# Nguyen_Ly.net
KiCad netlist of a schematic drawn in Altium Designer
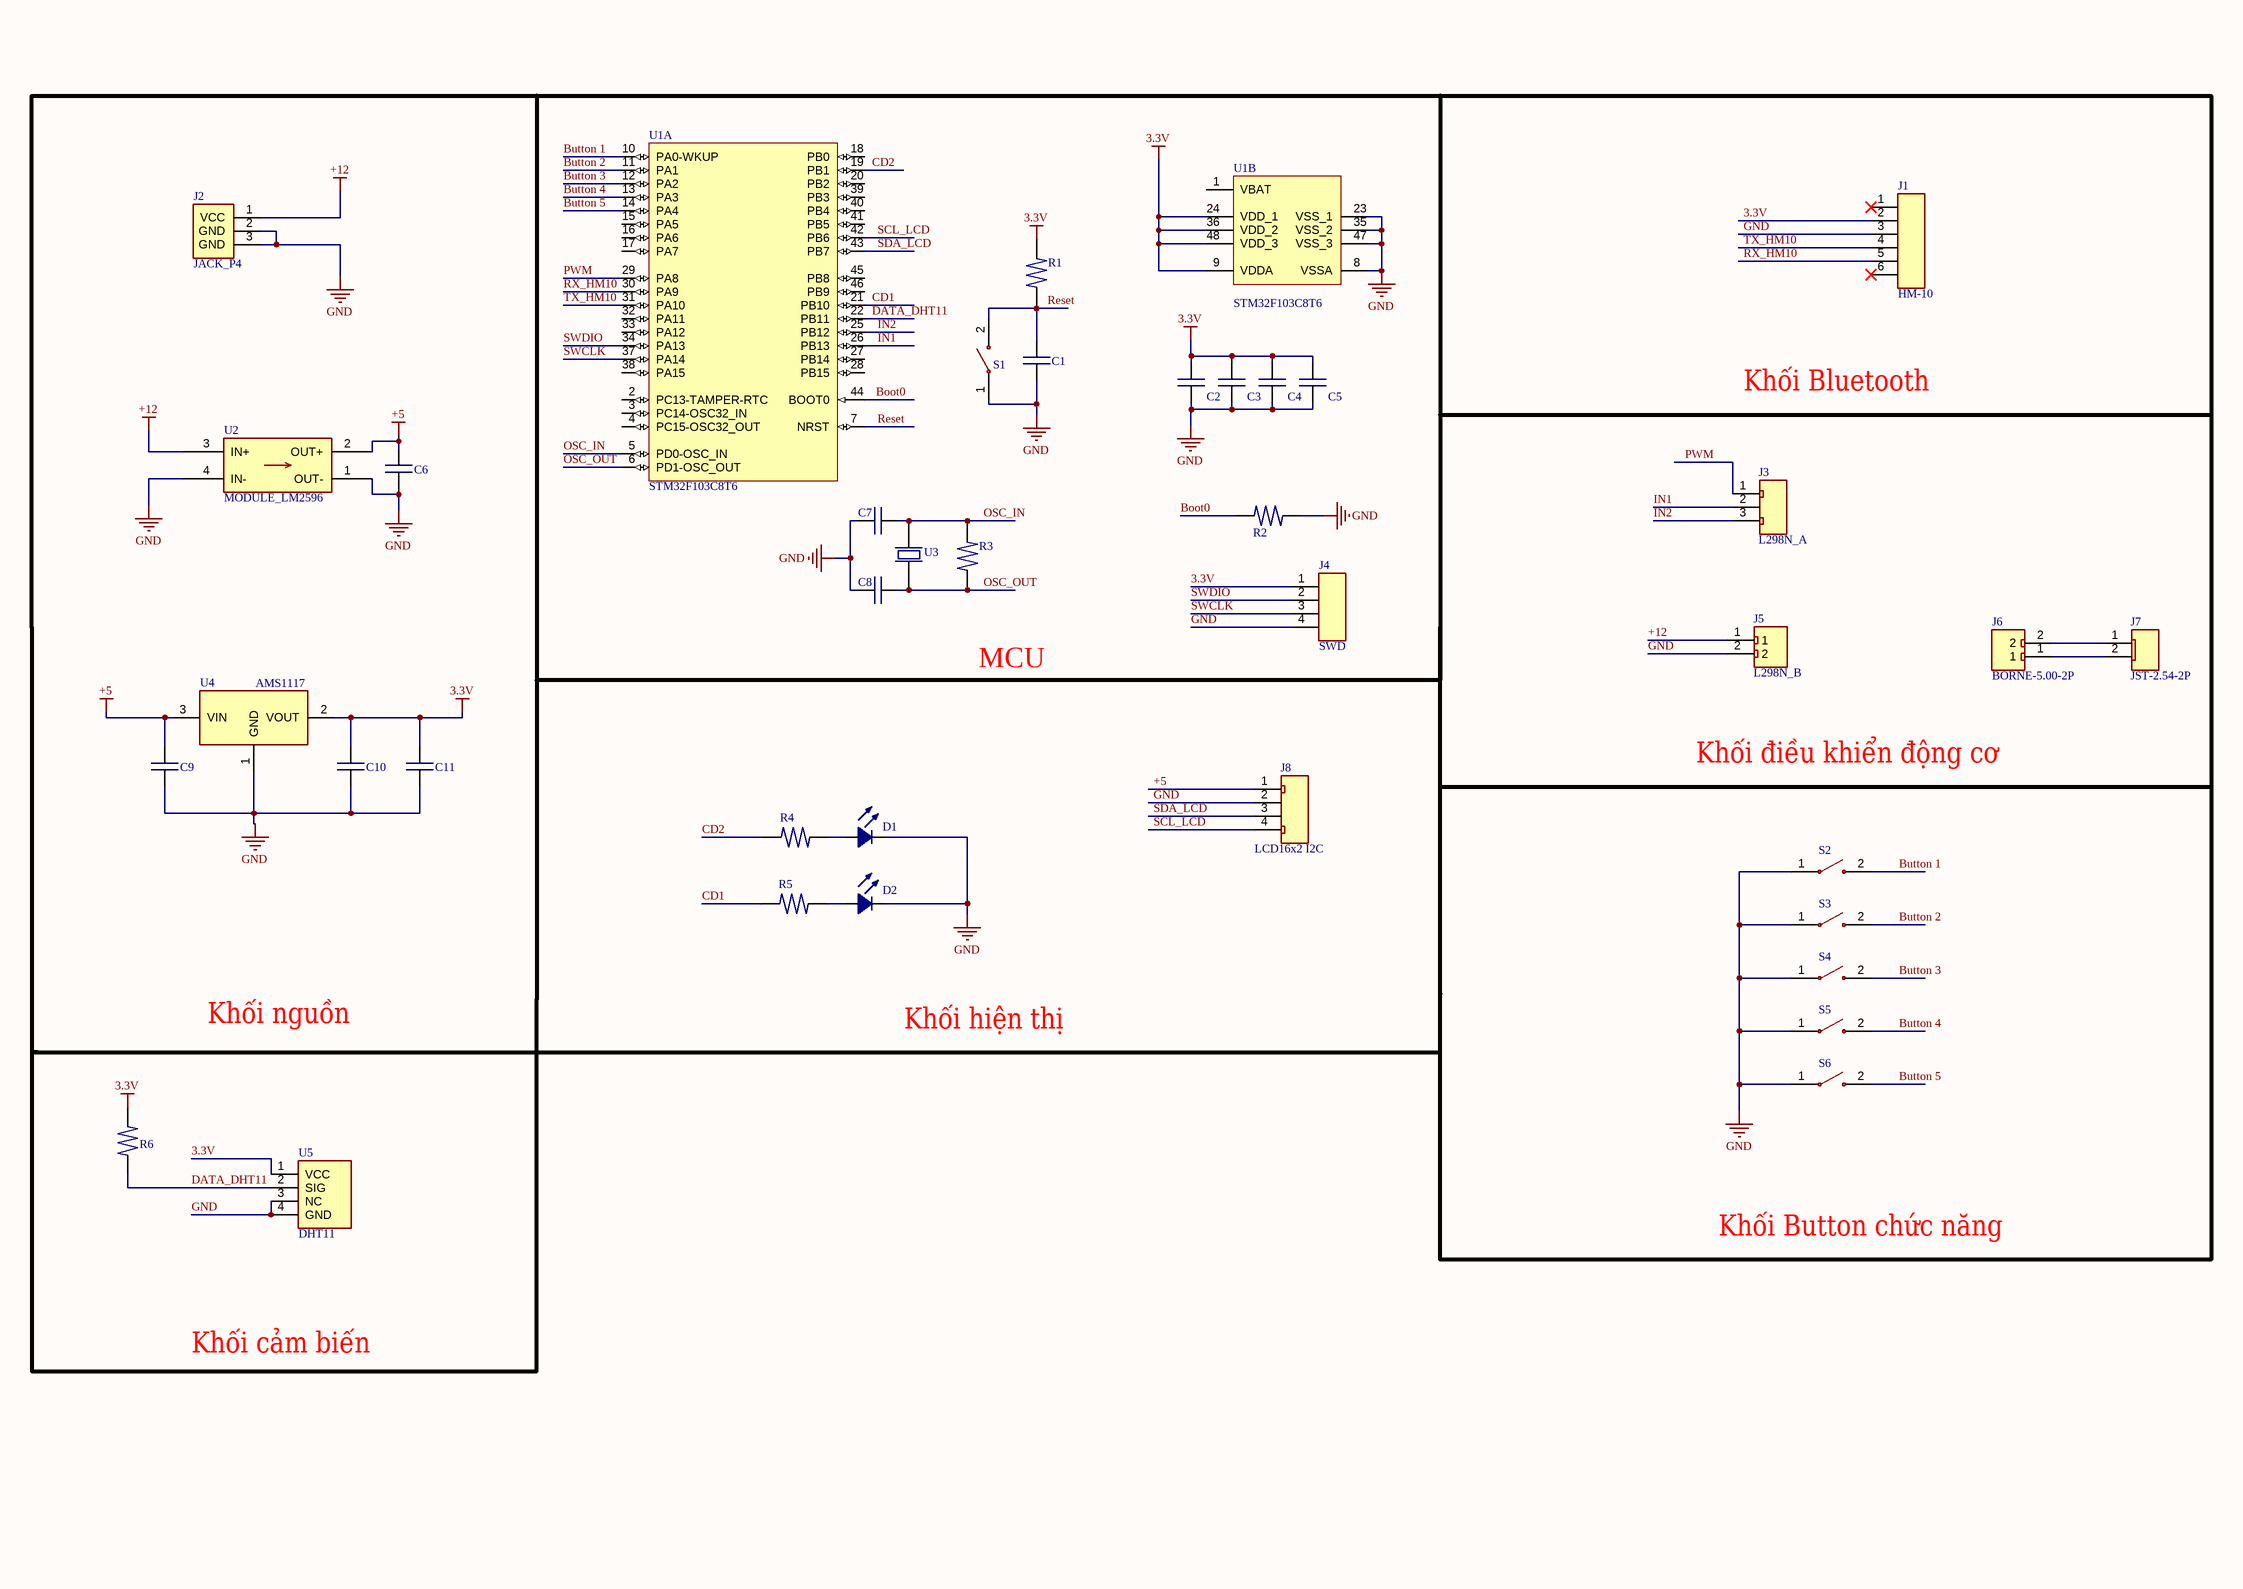
[diagram p0: Nguyen_Ly.SchDoc]

(export (version "E")
  (design (tool "Eeschema 10.0.6"))
  (components
    (comp (ref "C1")
      (value "CAPCITOR 104")
      (footprint "CAPACITOR 104")
      (description "Ceramic Capacitor 104, 3mm.")
      (libsource (lib "MyComponents") (part "CAPACITOR 104"))
    )
    (comp (ref "C2")
      (value "CAPACITOR 0603")
      (footprint "CAPACITOR 0603")
      (description "Generic Capacitor 0603, 1.6x0.8x0.9mm.")
      (libsource (lib "MyComponents") (part "CAPACITOR 0603"))
    )
    (comp (ref "C3")
      (value "CAPACITOR 0603")
      (footprint "CAPACITOR 0603")
      (description "Generic Capacitor 0603, 1.6x0.8x0.9mm.")
      (libsource (lib "MyComponents") (part "CAPACITOR 0603"))
    )
    (comp (ref "C4")
      (value "CAPACITOR 0603")
      (footprint "CAPACITOR 0603")
      (description "Generic Capacitor 0603, 1.6x0.8x0.9mm.")
      (libsource (lib "MyComponents") (part "CAPACITOR 0603"))
    )
    (comp (ref "C5")
      (value "CAPACITOR 0603")
      (footprint "CAPACITOR 0603")
      (description "Generic Capacitor 0603, 1.6x0.8x0.9mm.")
      (libsource (lib "MyComponents") (part "CAPACITOR 0603"))
    )
    (comp (ref "C6")
      (value "CAPCITOR 104")
      (footprint "CAPACITOR 104")
      (description "Ceramic Capacitor 104, 3mm.")
      (libsource (lib "MyComponents") (part "CAPACITOR 104"))
    )
    (comp (ref "C7")
      (value "CAPACITOR 0603")
      (footprint "CAPACITOR 0603")
      (description "Generic Capacitor 0603, 1.6x0.8x0.9mm.")
      (libsource (lib "MyComponents") (part "CAPACITOR 0603"))
    )
    (comp (ref "C8")
      (value "CAPACITOR 0603")
      (footprint "CAPACITOR 0603")
      (description "Generic Capacitor 0603, 1.6x0.8x0.9mm.")
      (libsource (lib "MyComponents") (part "CAPACITOR 0603"))
    )
    (comp (ref "C9")
      (value "CAPACITOR 0603")
      (footprint "CAPACITOR 0603")
      (description "Generic Capacitor 0603, 1.6x0.8x0.9mm.")
      (libsource (lib "MyComponents") (part "CAPACITOR 0603"))
    )
    (comp (ref "C10")
      (value "CAPACITOR 0603")
      (footprint "CAPACITOR 0603")
      (description "Generic Capacitor 0603, 1.6x0.8x0.9mm.")
      (libsource (lib "MyComponents") (part "CAPACITOR 0603"))
    )
    (comp (ref "C11")
      (value "CAPACITOR 0603")
      (footprint "CAPACITOR 0603")
      (description "Generic Capacitor 0603, 1.6x0.8x0.9mm.")
      (libsource (lib "MyComponents") (part "CAPACITOR 0603"))
    )
    (comp (ref "D1")
      (value "LED_5mm_YELLOW")
      (footprint "LED_5mm_YELLOW")
      (description "LED PTH 5mm Yellow.")
      (libsource (lib "MyComponents") (part "LED_5mm_YELLOW"))
    )
    (comp (ref "D2")
      (value "LED_5mm_RED")
      (footprint "LED_5mm_RED")
      (description "LED PTH 5mm Red.")
      (libsource (lib "MyComponents") (part "LED_5mm_RED"))
    )
    (comp (ref "J1")
      (value "HM-10")
      (footprint "FEMALE-2.54-6P")
      (description "Female Header Connector 2.54mm 6 Pins.")
      (libsource (lib "MyComponents") (part "FEMALE-2.54-6P"))
    )
    (comp (ref "J2")
      (value "JACK_P4")
      (footprint "JACK_P4")
      (description "9V Battery Connector Jack P4.")
      (libsource (lib "MyComponents") (part "JACK_P4"))
    )
    (comp (ref "J3")
      (value "L298N_A")
      (footprint "JST-2.54-3P")
      (description "Female Connector JST 3 Vias, 2.54mm.")
      (libsource (lib "MyComponents") (part "JST-2.54-3P"))
    )
    (comp (ref "J4")
      (value "SWD")
      (footprint "MALE-2.54-4P")
      (description "Male Header Connector 2.54mm 4 Pins.")
      (libsource (lib "MyComponents") (part "MALE-2.54-4P"))
    )
    (comp (ref "J5")
      (value "L298N_B")
      (footprint "BORNE-5.00-2P")
      (description "Borne 2 Vias, Pitch 5mm.")
      (libsource (lib "") (part "BORNE-5.00-2P_1"))
    )
    (comp (ref "J6")
      (value "BORNE-5.00-2P")
      (footprint "BORNE-5.00-2P")
      (description "Borne 2 Vias, Pitch 5mm.")
      (libsource (lib "MyComponents") (part "BORNE-5.00-2P"))
    )
    (comp (ref "J7")
      (value "JST-2.54-2P")
      (footprint "JST-2.54-2P")
      (description "Female Connector JST 2 Vias, 2.54mm.")
      (libsource (lib "MyComponents") (part "JST-2.54-2P"))
    )
    (comp (ref "J8")
      (value "LCD16x2 I2C")
      (footprint "JST-2.54-4P")
      (description "Female Connector JST 4 Vias, 2.54mm.")
      (libsource (lib "MyComponents") (part "JST-2.54-4P"))
    )
    (comp (ref "R1")
      (value "RESISTOR_9.5mm")
      (footprint "RESISTOR_PTH_9.5mm")
      (description "Generic Resistor 9.5mm.")
      (libsource (lib "MyComponents") (part "RESISTOR_9.5mm"))
    )
    (comp (ref "R2")
      (value "RESISTOR_0603")
      (footprint "RESISTOR_0603")
      (description "Generic Resistor 0603.")
      (libsource (lib "MyComponents") (part "RESISTOR_0603"))
    )
    (comp (ref "R3")
      (value "RESISTOR_0603")
      (footprint "RESISTOR_0603")
      (description "Generic Resistor 0603.")
      (libsource (lib "MyComponents") (part "RESISTOR_0603"))
    )
    (comp (ref "R4")
      (value "RESISTOR_9.5mm")
      (footprint "RESISTOR_PTH_9.5mm")
      (description "Generic Resistor 9.5mm.")
      (libsource (lib "MyComponents") (part "RESISTOR_9.5mm"))
    )
    (comp (ref "R5")
      (value "RESISTOR_9.5mm")
      (footprint "RESISTOR_PTH_9.5mm")
      (description "Generic Resistor 9.5mm.")
      (libsource (lib "MyComponents") (part "RESISTOR_9.5mm"))
    )
    (comp (ref "R6")
      (value "RESISTOR_9.5mm")
      (footprint "RESISTOR_PTH_9.5mm")
      (description "Generic Resistor 9.5mm.")
      (libsource (lib "MyComponents") (part "RESISTOR_9.5mm"))
    )
    (comp (ref "S1")
      (value "PUSH_BUTTON_6X6")
      (footprint "PUSH_BUTTON_6X6")
      (description "Push Button Tactile Switch PTH 4 Pins 6x6mm.")
      (libsource (lib "") (part "PUSH_BUTTON_6X6_1"))
    )
    (comp (ref "S2")
      (value "PUSH_BUTTON_6X6")
      (footprint "PUSH_BUTTON_6X6")
      (description "Push Button Tactile Switch PTH 4 Pins 6x6mm.")
      (libsource (lib "MyComponents") (part "PUSH_BUTTON_6X6"))
    )
    (comp (ref "S3")
      (value "PUSH_BUTTON_6X6")
      (footprint "PUSH_BUTTON_6X6")
      (description "Push Button Tactile Switch PTH 4 Pins 6x6mm.")
      (libsource (lib "MyComponents") (part "PUSH_BUTTON_6X6"))
    )
    (comp (ref "S4")
      (value "PUSH_BUTTON_6X6")
      (footprint "PUSH_BUTTON_6X6")
      (description "Push Button Tactile Switch PTH 4 Pins 6x6mm.")
      (libsource (lib "MyComponents") (part "PUSH_BUTTON_6X6"))
    )
    (comp (ref "S5")
      (value "PUSH_BUTTON_6X6")
      (footprint "PUSH_BUTTON_6X6")
      (description "Push Button Tactile Switch PTH 4 Pins 6x6mm.")
      (libsource (lib "MyComponents") (part "PUSH_BUTTON_6X6"))
    )
    (comp (ref "S6")
      (value "PUSH_BUTTON_6X6")
      (footprint "PUSH_BUTTON_6X6")
      (description "Push Button Tactile Switch PTH 4 Pins 6x6mm.")
      (libsource (lib "MyComponents") (part "PUSH_BUTTON_6X6"))
    )
    (comp (ref "U1")
      (value "STM32F103C8T6")
      (footprint "STM-LQFP48_N")
      (libsource (lib "STMicroelectronics STM32 F1") (part "STM32F103C8T6"))
    )
    (comp (ref "U2")
      (value "MODULE_LM2596")
      (footprint "MODULE_LM2596")
      (description "MODULE BUCK STEP DOWN 3A 43x20mm")
      (libsource (lib "MyComponents") (part "MODULE_LM2596"))
    )
    (comp (ref "U3")
      (value "CRISTAL_16Mhz")
      (footprint "CRISTAL_16Mhz_SMD")
      (description "CRYSTAL 16MHZ, PTH and SMD")
      (libsource (lib "MyComponents") (part "CRISTAL_16Mhz"))
    )
    (comp (ref "U4")
      (value "AMS1117")
      (footprint "AMS1117")
      (description "IC REG LINEAR 1A SOT-89-3L")
      (libsource (lib "MyComponents") (part "AMS1117"))
    )
    (comp (ref "U5")
      (value "DHT11")
      (footprint "DHT11")
      (description "SENSOR HUMIDITY/TEMPERATURE")
      (libsource (lib "MyComponents") (part "DHT11"))
    )
  )
  (nets
    (net (code "1") (name "+5") (class "Default")
      (node (ref "C6") (pin "2") (pinfunction "2_2") (pintype "passive"))
      (node (ref "C9") (pin "2") (pinfunction "2_2") (pintype "passive"))
      (node (ref "J8") (pin "1") (pintype "passive"))
      (node (ref "U2") (pin "2") (pinfunction "OUT+_2") (pintype "passive"))
      (node (ref "U4") (pin "3") (pinfunction "VIN_3") (pintype "passive"))
    )
    (net (code "2") (name "+12") (class "Default")
      (node (ref "J2") (pin "1") (pinfunction "VCC_1") (pintype "passive"))
      (node (ref "J5") (pin "1") (pinfunction "1_1") (pintype "passive"))
      (node (ref "U2") (pin "3") (pinfunction "IN+_3") (pintype "passive"))
    )
    (net (code "3") (name "/Boot0") (class "Default")
      (node (ref "R2") (pin "2") (pinfunction "2_2") (pintype "passive"))
      (node (ref "U1") (pin "44") (pinfunction "BOOT0_44") (pintype "input"))
    )
    (net (code "4") (name "/Button 1") (class "Default")
      (node (ref "S2") (pin "2") (pinfunction "2_2") (pintype "passive"))
      (node (ref "U1") (pin "10") (pinfunction "PA0-WKUP_10") (pintype "bidirectional"))
    )
    (net (code "5") (name "/Button 2") (class "Default")
      (node (ref "S3") (pin "2") (pinfunction "2_2") (pintype "passive"))
      (node (ref "U1") (pin "11") (pinfunction "PA1_11") (pintype "bidirectional"))
    )
    (net (code "6") (name "/Button 3") (class "Default")
      (node (ref "S4") (pin "2") (pinfunction "2_2") (pintype "passive"))
      (node (ref "U1") (pin "12") (pinfunction "PA2_12") (pintype "bidirectional"))
    )
    (net (code "7") (name "/Button 4") (class "Default")
      (node (ref "S5") (pin "2") (pinfunction "2_2") (pintype "passive"))
      (node (ref "U1") (pin "13") (pinfunction "PA3_13") (pintype "bidirectional"))
    )
    (net (code "8") (name "/Button 5") (class "Default")
      (node (ref "S6") (pin "2") (pinfunction "2_2") (pintype "passive"))
      (node (ref "U1") (pin "14") (pinfunction "PA4_14") (pintype "bidirectional"))
    )
    (net (code "9") (name "/CD1") (class "Default")
      (node (ref "R5") (pin "1") (pinfunction "1_1") (pintype "passive"))
      (node (ref "U1") (pin "21") (pinfunction "PB10_21") (pintype "bidirectional"))
    )
    (net (code "10") (name "/CD2") (class "Default")
      (node (ref "R4") (pin "1") (pinfunction "1_1") (pintype "passive"))
      (node (ref "U1") (pin "19") (pinfunction "PB1_19") (pintype "bidirectional"))
    )
    (net (code "11") (name "/DATA_DHT11") (class "Default")
      (node (ref "R6") (pin "1") (pinfunction "1_1") (pintype "passive"))
      (node (ref "U1") (pin "22") (pinfunction "PB11_22") (pintype "bidirectional"))
      (node (ref "U5") (pin "2") (pinfunction "SIG_2") (pintype "passive"))
    )
    (net (code "12") (name "/IN1") (class "Default")
      (node (ref "J3") (pin "2") (pintype "passive"))
      (node (ref "U1") (pin "26") (pinfunction "PB13_26") (pintype "bidirectional"))
    )
    (net (code "13") (name "/IN2") (class "Default")
      (node (ref "J3") (pin "3") (pintype "passive"))
      (node (ref "U1") (pin "25") (pinfunction "PB12_25") (pintype "bidirectional"))
    )
    (net (code "14") (name "/OSC_IN") (class "Default")
      (node (ref "C7") (pin "2") (pinfunction "2_2") (pintype "passive"))
      (node (ref "R3") (pin "2") (pinfunction "2_2") (pintype "passive"))
      (node (ref "U1") (pin "5") (pinfunction "PD0-OSC_IN_5") (pintype "bidirectional"))
      (node (ref "U3") (pin "2") (pinfunction "2_2") (pintype "power_in"))
    )
    (net (code "15") (name "/OSC_OUT") (class "Default")
      (node (ref "C8") (pin "2") (pinfunction "2_2") (pintype "passive"))
      (node (ref "R3") (pin "1") (pinfunction "1_1") (pintype "passive"))
      (node (ref "U1") (pin "6") (pinfunction "PD1-OSC_OUT_6") (pintype "bidirectional"))
      (node (ref "U3") (pin "1") (pinfunction "1_1") (pintype "power_in"))
    )
    (net (code "16") (name "/PWM") (class "Default")
      (node (ref "J3") (pin "1") (pintype "passive"))
      (node (ref "U1") (pin "29") (pinfunction "PA8_29") (pintype "bidirectional"))
    )
    (net (code "17") (name "/RX_HM10") (class "Default")
      (node (ref "J1") (pin "5") (pintype "passive"))
      (node (ref "U1") (pin "30") (pinfunction "PA9_30") (pintype "bidirectional"))
    )
    (net (code "18") (name "/Reset") (class "Default")
      (node (ref "C1") (pin "2") (pinfunction "2_2") (pintype "passive"))
      (node (ref "R1") (pin "1") (pinfunction "1_1") (pintype "passive"))
      (node (ref "S1") (pin "2") (pinfunction "2_2") (pintype "passive"))
      (node (ref "U1") (pin "7") (pinfunction "NRST_7") (pintype "bidirectional"))
    )
    (net (code "19") (name "/SCL_LCD") (class "Default")
      (node (ref "J8") (pin "4") (pintype "passive"))
      (node (ref "U1") (pin "42") (pinfunction "PB6_42") (pintype "bidirectional"))
    )
    (net (code "20") (name "/SDA_LCD") (class "Default")
      (node (ref "J8") (pin "3") (pintype "passive"))
      (node (ref "U1") (pin "43") (pinfunction "PB7_43") (pintype "bidirectional"))
    )
    (net (code "21") (name "/SWCLK") (class "Default")
      (node (ref "J4") (pin "3") (pintype "passive"))
      (node (ref "U1") (pin "37") (pinfunction "PA14_37") (pintype "bidirectional"))
    )
    (net (code "22") (name "/SWDIO") (class "Default")
      (node (ref "J4") (pin "2") (pintype "passive"))
      (node (ref "U1") (pin "34") (pinfunction "PA13_34") (pintype "bidirectional"))
    )
    (net (code "23") (name "/TX_HM10") (class "Default")
      (node (ref "J1") (pin "4") (pintype "passive"))
      (node (ref "U1") (pin "31") (pinfunction "PA10_31") (pintype "bidirectional"))
    )
    (net (code "24") (name "3.3V") (class "Default")
      (node (ref "C10") (pin "2") (pinfunction "2_2") (pintype "passive"))
      (node (ref "C11") (pin "2") (pinfunction "2_2") (pintype "passive"))
      (node (ref "C2") (pin "2") (pinfunction "2_2") (pintype "passive"))
      (node (ref "C3") (pin "2") (pinfunction "2_2") (pintype "passive"))
      (node (ref "C4") (pin "2") (pinfunction "2_2") (pintype "passive"))
      (node (ref "C5") (pin "2") (pinfunction "2_2") (pintype "passive"))
      (node (ref "J1") (pin "2") (pintype "passive"))
      (node (ref "J4") (pin "1") (pintype "passive"))
      (node (ref "R1") (pin "2") (pinfunction "2_2") (pintype "passive"))
      (node (ref "R6") (pin "2") (pinfunction "2_2") (pintype "passive"))
      (node (ref "U1") (pin "24") (pinfunction "VDD_1_24") (pintype "power_in"))
      (node (ref "U1") (pin "36") (pinfunction "VDD_2_36") (pintype "power_in"))
      (node (ref "U1") (pin "48") (pinfunction "VDD_3_48") (pintype "power_in"))
      (node (ref "U1") (pin "9") (pinfunction "VDDA_9") (pintype "power_in"))
      (node (ref "U4") (pin "2") (pinfunction "VOUT_2") (pintype "passive"))
      (node (ref "U5") (pin "1") (pinfunction "VCC_1") (pintype "passive"))
    )
    (net (code "25") (name "GND") (class "Default")
      (node (ref "C1") (pin "1") (pinfunction "1_1") (pintype "passive"))
      (node (ref "C10") (pin "1") (pinfunction "1_1") (pintype "passive"))
      (node (ref "C11") (pin "1") (pinfunction "1_1") (pintype "passive"))
      (node (ref "C2") (pin "1") (pinfunction "1_1") (pintype "passive"))
      (node (ref "C3") (pin "1") (pinfunction "1_1") (pintype "passive"))
      (node (ref "C4") (pin "1") (pinfunction "1_1") (pintype "passive"))
      (node (ref "C5") (pin "1") (pinfunction "1_1") (pintype "passive"))
      (node (ref "C6") (pin "1") (pinfunction "1_1") (pintype "passive"))
      (node (ref "C7") (pin "1") (pinfunction "1_1") (pintype "passive"))
      (node (ref "C8") (pin "1") (pinfunction "1_1") (pintype "passive"))
      (node (ref "C9") (pin "1") (pinfunction "1_1") (pintype "passive"))
      (node (ref "D1") (pin "2") (pinfunction "2_2") (pintype "passive"))
      (node (ref "D2") (pin "2") (pinfunction "2_2") (pintype "passive"))
      (node (ref "J1") (pin "3") (pintype "passive"))
      (node (ref "J2") (pin "2") (pinfunction "GND_2") (pintype "passive"))
      (node (ref "J2") (pin "3") (pinfunction "GND_3") (pintype "passive"))
      (node (ref "J4") (pin "4") (pintype "passive"))
      (node (ref "J5") (pin "2") (pinfunction "2_2") (pintype "passive"))
      (node (ref "J8") (pin "2") (pintype "passive"))
      (node (ref "R2") (pin "1") (pinfunction "1_1") (pintype "passive"))
      (node (ref "S1") (pin "1") (pinfunction "1_1") (pintype "passive"))
      (node (ref "S2") (pin "1") (pinfunction "1_1") (pintype "passive"))
      (node (ref "S3") (pin "1") (pinfunction "1_1") (pintype "passive"))
      (node (ref "S4") (pin "1") (pinfunction "1_1") (pintype "passive"))
      (node (ref "S5") (pin "1") (pinfunction "1_1") (pintype "passive"))
      (node (ref "S6") (pin "1") (pinfunction "1_1") (pintype "passive"))
      (node (ref "U1") (pin "23") (pinfunction "VSS_1_23") (pintype "power_in"))
      (node (ref "U1") (pin "35") (pinfunction "VSS_2_35") (pintype "power_in"))
      (node (ref "U1") (pin "47") (pinfunction "VSS_3_47") (pintype "power_in"))
      (node (ref "U1") (pin "8") (pinfunction "VSSA_8") (pintype "power_in"))
      (node (ref "U2") (pin "1") (pinfunction "OUT-_1") (pintype "passive"))
      (node (ref "U2") (pin "4") (pinfunction "IN-_4") (pintype "passive"))
      (node (ref "U4") (pin "1") (pinfunction "GND_1") (pintype "passive"))
      (node (ref "U5") (pin "3") (pinfunction "NC_3") (pintype "passive"))
      (node (ref "U5") (pin "4") (pinfunction "GND_4") (pintype "passive"))
    )
    (net (code "26") (name "Net-(D1-Pad1)") (class "Default")
      (node (ref "D1") (pin "1") (pinfunction "1_1") (pintype "passive"))
      (node (ref "R4") (pin "2") (pinfunction "2_2") (pintype "passive"))
    )
    (net (code "27") (name "Net-(D2-Pad1)") (class "Default")
      (node (ref "D2") (pin "1") (pinfunction "1_1") (pintype "passive"))
      (node (ref "R5") (pin "2") (pinfunction "2_2") (pintype "passive"))
    )
    (net (code "28") (name "Net-(J6-Pad1)") (class "Default")
      (node (ref "J6") (pin "1") (pinfunction "1_1") (pintype "passive"))
      (node (ref "J7") (pin "2") (pintype "passive"))
    )
    (net (code "29") (name "Net-(J6-Pad2)") (class "Default")
      (node (ref "J6") (pin "2") (pinfunction "2_2") (pintype "passive"))
      (node (ref "J7") (pin "1") (pintype "passive"))
    )
    (net (code "30") (name "unconnected-(J1-Pad1)") (class "Default")
      (node (ref "J1") (pin "1") (pintype "passive+no_connect"))
    )
    (net (code "31") (name "unconnected-(J1-Pad6)") (class "Default")
      (node (ref "J1") (pin "6") (pintype "passive+no_connect"))
    )
    (net (code "32") (name "unconnected-(U1A-PA5-Pad15)") (class "Default")
      (node (ref "U1") (pin "15") (pinfunction "PA5_15") (pintype "bidirectional"))
    )
    (net (code "33") (name "unconnected-(U1A-PA6-Pad16)") (class "Default")
      (node (ref "U1") (pin "16") (pinfunction "PA6_16") (pintype "bidirectional"))
    )
    (net (code "34") (name "unconnected-(U1A-PA7-Pad17)") (class "Default")
      (node (ref "U1") (pin "17") (pinfunction "PA7_17") (pintype "bidirectional"))
    )
    (net (code "35") (name "unconnected-(U1A-PA11-Pad32)") (class "Default")
      (node (ref "U1") (pin "32") (pinfunction "PA11_32") (pintype "bidirectional"))
    )
    (net (code "36") (name "unconnected-(U1A-PA12-Pad33)") (class "Default")
      (node (ref "U1") (pin "33") (pinfunction "PA12_33") (pintype "bidirectional"))
    )
    (net (code "37") (name "unconnected-(U1A-PA15-Pad38)") (class "Default")
      (node (ref "U1") (pin "38") (pinfunction "PA15_38") (pintype "bidirectional"))
    )
    (net (code "38") (name "unconnected-(U1A-PB0-Pad18)") (class "Default")
      (node (ref "U1") (pin "18") (pinfunction "PB0_18") (pintype "bidirectional"))
    )
    (net (code "39") (name "unconnected-(U1A-PB2-Pad20)") (class "Default")
      (node (ref "U1") (pin "20") (pinfunction "PB2_20") (pintype "bidirectional"))
    )
    (net (code "40") (name "unconnected-(U1A-PB3-Pad39)") (class "Default")
      (node (ref "U1") (pin "39") (pinfunction "PB3_39") (pintype "bidirectional"))
    )
    (net (code "41") (name "unconnected-(U1A-PB4-Pad40)") (class "Default")
      (node (ref "U1") (pin "40") (pinfunction "PB4_40") (pintype "bidirectional"))
    )
    (net (code "42") (name "unconnected-(U1A-PB5-Pad41)") (class "Default")
      (node (ref "U1") (pin "41") (pinfunction "PB5_41") (pintype "bidirectional"))
    )
    (net (code "43") (name "unconnected-(U1A-PB8-Pad45)") (class "Default")
      (node (ref "U1") (pin "45") (pinfunction "PB8_45") (pintype "bidirectional"))
    )
    (net (code "44") (name "unconnected-(U1A-PB9-Pad46)") (class "Default")
      (node (ref "U1") (pin "46") (pinfunction "PB9_46") (pintype "bidirectional"))
    )
    (net (code "45") (name "unconnected-(U1A-PB14-Pad27)") (class "Default")
      (node (ref "U1") (pin "27") (pinfunction "PB14_27") (pintype "bidirectional"))
    )
    (net (code "46") (name "unconnected-(U1A-PB15-Pad28)") (class "Default")
      (node (ref "U1") (pin "28") (pinfunction "PB15_28") (pintype "bidirectional"))
    )
    (net (code "47") (name "unconnected-(U1A-PC13-TAMPER-RTC-Pad2)") (class "Default")
      (node (ref "U1") (pin "2") (pinfunction "PC13-TAMPER-RTC_2") (pintype "bidirectional"))
    )
    (net (code "48") (name "unconnected-(U1A-PC14-OSC32_IN-Pad3)") (class "Default")
      (node (ref "U1") (pin "3") (pinfunction "PC14-OSC32_IN_3") (pintype "bidirectional"))
    )
    (net (code "49") (name "unconnected-(U1A-PC15-OSC32_OUT-Pad4)") (class "Default")
      (node (ref "U1") (pin "4") (pinfunction "PC15-OSC32_OUT_4") (pintype "bidirectional"))
    )
    (net (code "50") (name "unconnected-(U1B-VBAT-Pad1)") (class "Default")
      (node (ref "U1") (pin "1") (pinfunction "VBAT_1") (pintype "power_in"))
    )
  )
)
